# pi_mcu_powerBoard.net
KiCad netlist of a schematic drawn in EAGLE
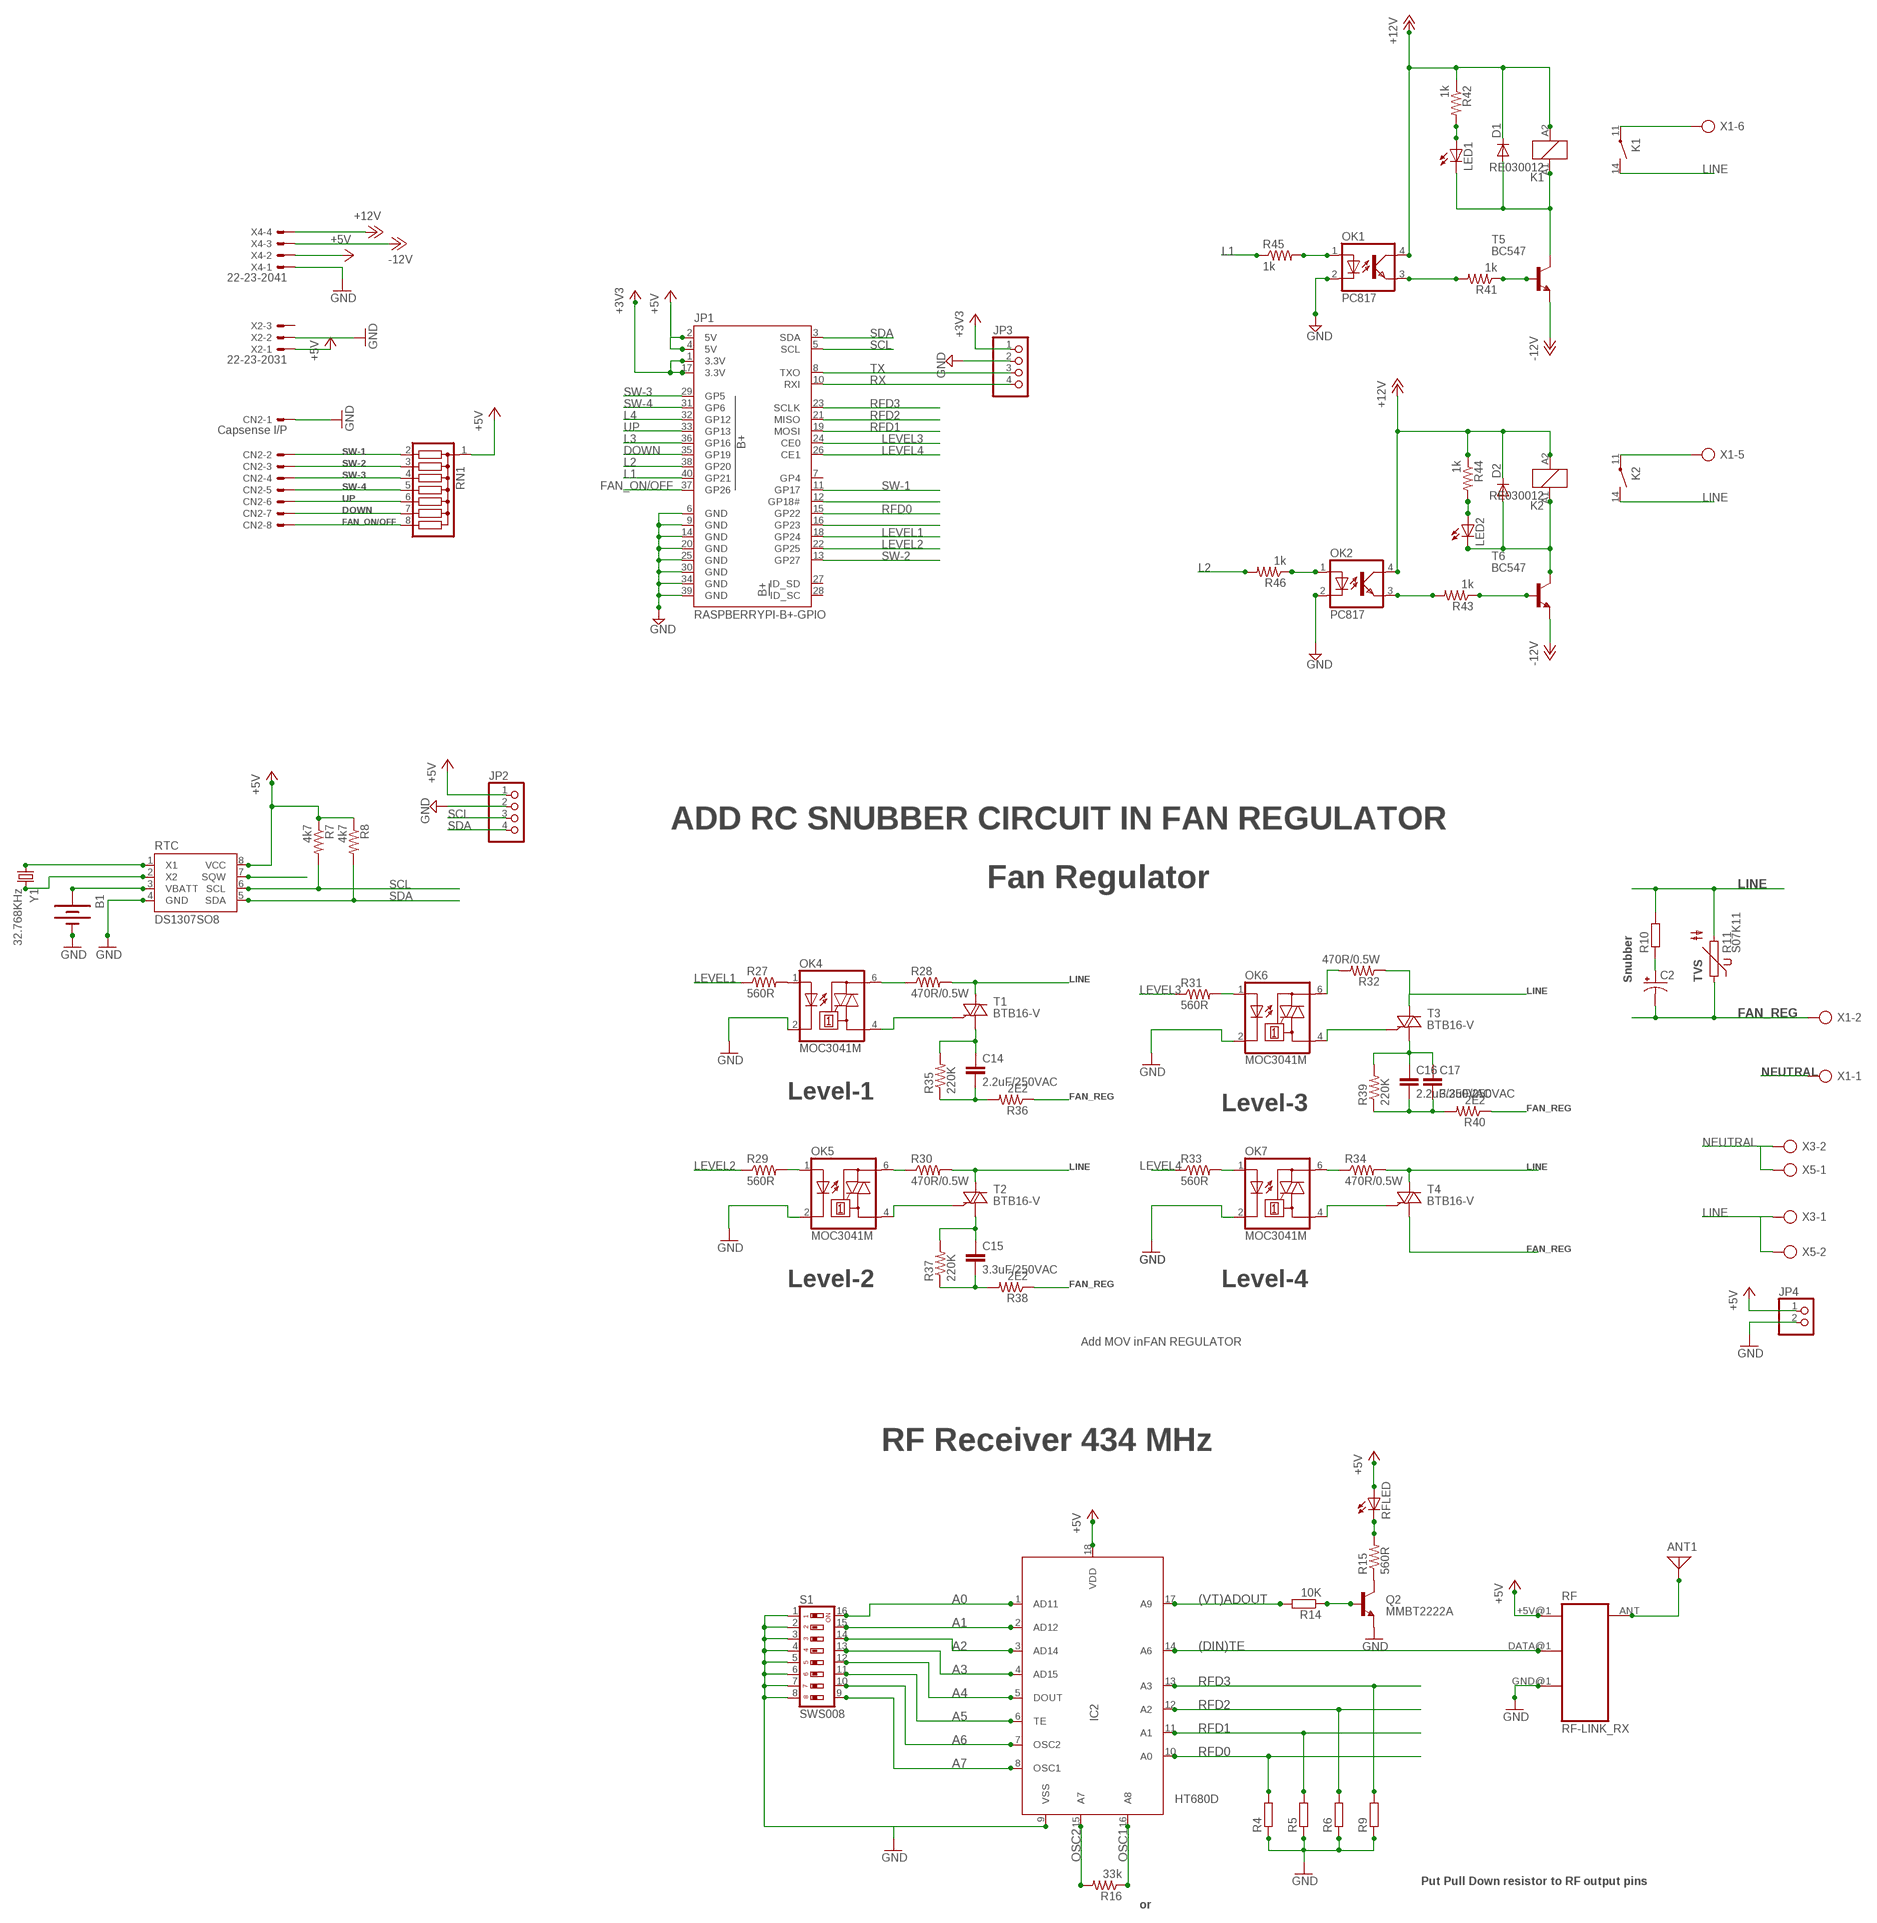
[diagram p0: schematic, sheet 1, part 1 of 2]
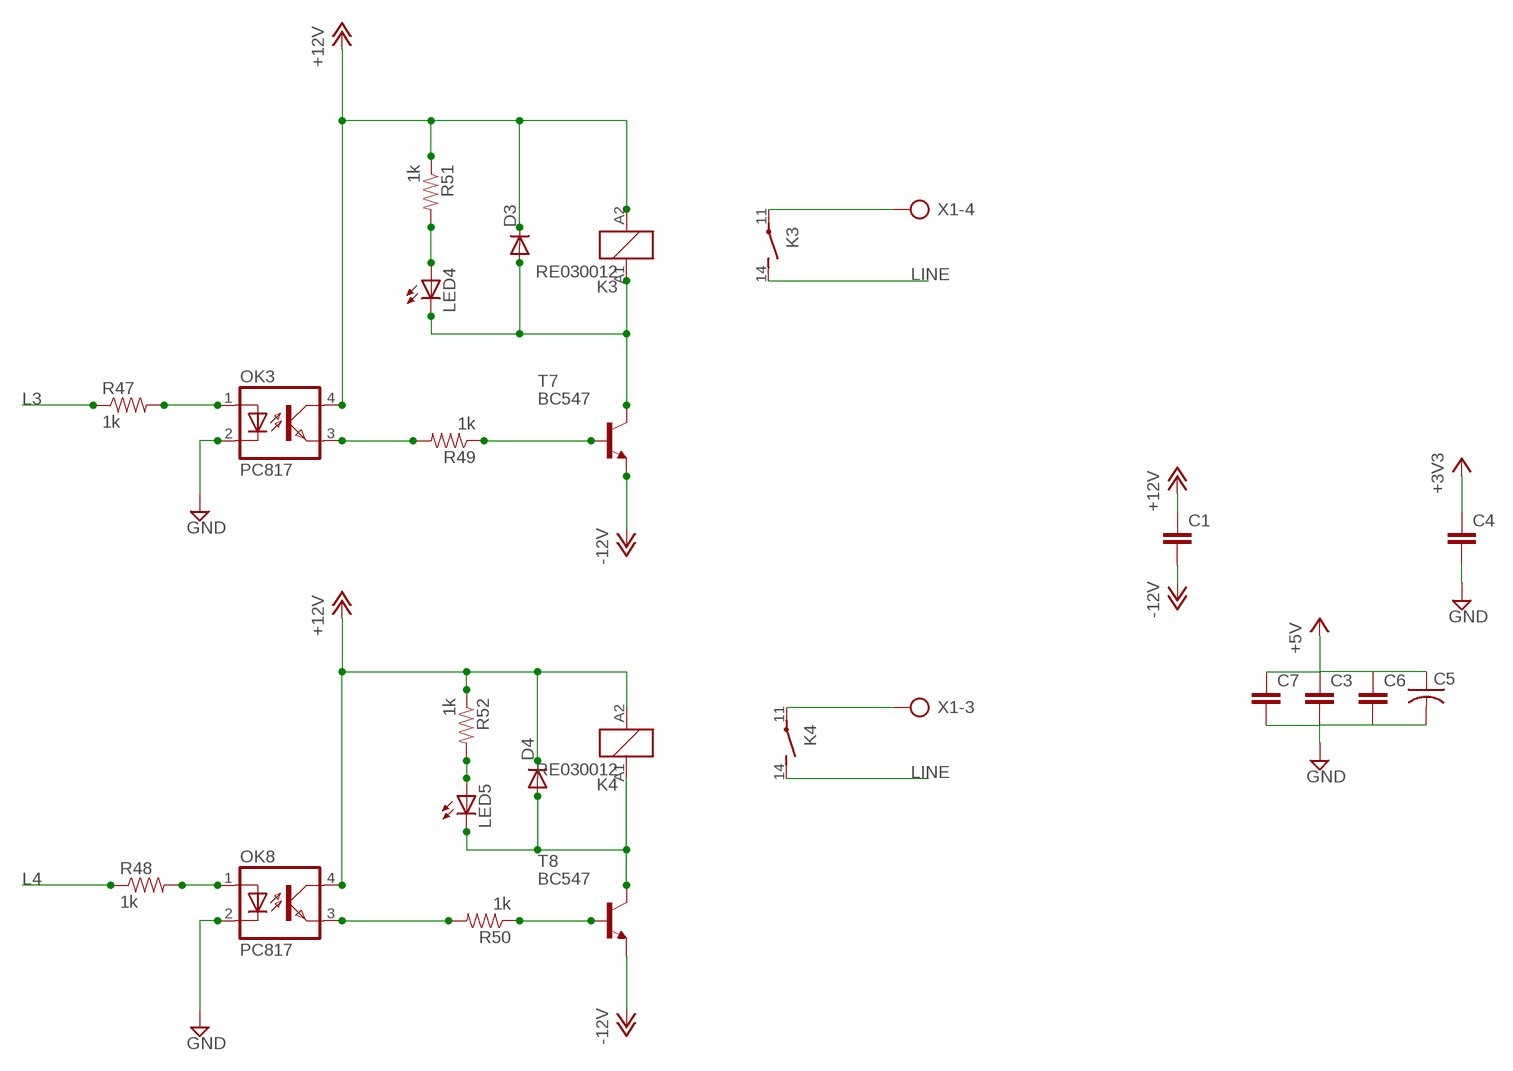
[diagram p1: schematic, sheet 1, part 2 of 2]

(export (version "E")
  (design (tool "Eeschema 10.0.6"))
  (components
    (comp (ref "ANT1")
      (value "ANTENNA")
      (footprint "eagle-import:PAD-01")
      (libsource (lib "eagle-import") (part "ANTENNA"))
    )
    (comp (ref "B1")
      (value "BATTERY20SMD")
      (footprint "eagle-import:BATTCON_20MM")
      (libsource (lib "eagle-import") (part "BATTERY20SMD"))
    )
    (comp (ref "C1")
      (value "C-EUC1206")
      (footprint "eagle-import:C1206")
      (libsource (lib "eagle-import") (part "C-EUC1206"))
    )
    (comp (ref "C2")
      (value "CPOL-USE5-9VAXIAL")
      (footprint "eagle-import:E5R")
      (libsource (lib "eagle-import") (part "CPOL-USE5-9VAXIAL"))
    )
    (comp (ref "C3")
      (value "C-EUC1206")
      (footprint "eagle-import:C1206")
      (libsource (lib "eagle-import") (part "C-EUC1206"))
    )
    (comp (ref "C4")
      (value "C-EUC1206")
      (footprint "eagle-import:C1206")
      (libsource (lib "eagle-import") (part "C-EUC1206"))
    )
    (comp (ref "C5")
      (value "C-USC1206")
      (footprint "eagle-import:C1206")
      (libsource (lib "eagle-import") (part "C-USC1206"))
    )
    (comp (ref "C6")
      (value "C-EUC1206")
      (footprint "eagle-import:C1206")
      (libsource (lib "eagle-import") (part "C-EUC1206"))
    )
    (comp (ref "C7")
      (value "C-EUC1206")
      (footprint "eagle-import:C1206")
      (libsource (lib "eagle-import") (part "C-EUC1206"))
    )
    (comp (ref "C14")
      (value "2.2uF/250VAC")
      (footprint "eagle-import:C27.5B9")
      (libsource (lib "eagle-import") (part "C27/9"))
    )
    (comp (ref "C15")
      (value "3.3uF/250VAC")
      (footprint "eagle-import:C27.5B9")
      (libsource (lib "eagle-import") (part "C27/9"))
    )
    (comp (ref "C16")
      (value "2.2uF/250VAC")
      (footprint "eagle-import:C27.5B9")
      (libsource (lib "eagle-import") (part "C27/9"))
    )
    (comp (ref "C17")
      (value "3.3uF/250VAC")
      (footprint "eagle-import:C27.5B9")
      (libsource (lib "eagle-import") (part "C27/9"))
    )
    (comp (ref "CN2")
      (value "Capsense I/P")
      (footprint "eagle-import:22-23-2081")
      (fields (field (name "MF") "MOLEX") (field (name "MPN") "22-23-2081"))
      (libsource (lib "eagle-import") (part "22-23-2081"))
    )
    (comp (ref "D1")
      (value "DIODE-D-2.5")
      (footprint "eagle-import:D-2.5")
      (libsource (lib "eagle-import") (part "DIODE-D-2.5"))
    )
    (comp (ref "D2")
      (value "DIODE-D-2.5")
      (footprint "eagle-import:D-2.5")
      (libsource (lib "eagle-import") (part "DIODE-D-2.5"))
    )
    (comp (ref "D3")
      (value "DIODE-D-2.5")
      (footprint "eagle-import:D-2.5")
      (libsource (lib "eagle-import") (part "DIODE-D-2.5"))
    )
    (comp (ref "D4")
      (value "DIODE-D-2.5")
      (footprint "eagle-import:D-2.5")
      (libsource (lib "eagle-import") (part "DIODE-D-2.5"))
    )
    (comp (ref "IC2")
      (value "HT680D")
      (footprint "eagle-import:SOP18")
      (libsource (lib "eagle-import") (part "HT680D"))
    )
    (comp (ref "JP1")
      (value "RASPBERRYPI-B+-GPIO")
      (footprint "eagle-import:2X20-SHROUDED")
      (libsource (lib "eagle-import") (part "RASPBERRYPI-B+-GPIO"))
    )
    (comp (ref "JP2")
      (value "PINHD-1X4")
      (footprint "eagle-import:1X04")
      (libsource (lib "eagle-import") (part "PINHD-1X4"))
    )
    (comp (ref "JP3")
      (value "PINHD-1X4")
      (footprint "eagle-import:1X04")
      (libsource (lib "eagle-import") (part "PINHD-1X4"))
    )
    (comp (ref "JP4")
      (value "PINHD-1X2")
      (footprint "eagle-import:1X02")
      (libsource (lib "eagle-import") (part "PINHD-1X2"))
    )
    (comp (ref "K1")
      (value "RE030012")
      (footprint "eagle-import:RE-SCHRACK")
      (fields (field (name "MF") "TYCO ELECTRONICS"))
      (libsource (lib "eagle-import") (part "RE030012"))
    )
    (comp (ref "K2")
      (value "RE030012")
      (footprint "eagle-import:RE-SCHRACK")
      (fields (field (name "MF") "TYCO ELECTRONICS"))
      (libsource (lib "eagle-import") (part "RE030012"))
    )
    (comp (ref "K3")
      (value "RE030012")
      (footprint "eagle-import:RE-SCHRACK")
      (fields (field (name "MF") "TYCO ELECTRONICS"))
      (libsource (lib "eagle-import") (part "RE030012"))
    )
    (comp (ref "K4")
      (value "RE030012")
      (footprint "eagle-import:RE-SCHRACK")
      (fields (field (name "MF") "TYCO ELECTRONICS"))
      (libsource (lib "eagle-import") (part "RE030012"))
    )
    (comp (ref "LED1")
      (value "LED3MM")
      (footprint "eagle-import:LED3MM")
      (libsource (lib "eagle-import") (part "LED3MM"))
    )
    (comp (ref "LED2")
      (value "LED3MM")
      (footprint "eagle-import:LED3MM")
      (libsource (lib "eagle-import") (part "LED3MM"))
    )
    (comp (ref "LED4")
      (value "LED3MM")
      (footprint "eagle-import:LED3MM")
      (libsource (lib "eagle-import") (part "LED3MM"))
    )
    (comp (ref "LED5")
      (value "LED3MM")
      (footprint "eagle-import:LED3MM")
      (libsource (lib "eagle-import") (part "LED3MM"))
    )
    (comp (ref "OK1")
      (value "PC817")
      (footprint "eagle-import:DIL04")
      (fields (field (name "MPN") "PC817X4J000F"))
      (libsource (lib "eagle-import") (part "PC817"))
    )
    (comp (ref "OK2")
      (value "PC817")
      (footprint "eagle-import:DIL04")
      (fields (field (name "MPN") "PC817X4J000F"))
      (libsource (lib "eagle-import") (part "PC817"))
    )
    (comp (ref "OK3")
      (value "PC817")
      (footprint "eagle-import:DIL04")
      (fields (field (name "MPN") "PC817X4J000F"))
      (libsource (lib "eagle-import") (part "PC817"))
    )
    (comp (ref "OK4")
      (value "MOC3041M")
      (footprint "eagle-import:DIL06")
      (fields
        (field (name "MF") "FAIRCHILD SEMICONDUCTOR")
        (field (name "MPN") "MOC3041M")
        (field (name "OC_FARNELL") "1086677")
        (field (name "OC_NEWARK") "78K6090")
      )
      (libsource (lib "eagle-import") (part "MOC3041M"))
    )
    (comp (ref "OK5")
      (value "MOC3041M")
      (footprint "eagle-import:DIL06")
      (fields
        (field (name "MF") "FAIRCHILD SEMICONDUCTOR")
        (field (name "MF_1") "FAIRCHILD SEMICONDUCTOR")
        (field (name "MPN") "MOC3031SM")
        (field (name "OC_FARNELL") "unknown")
        (field (name "OC_NEWARK") "34C1335")
      )
      (libsource (lib "eagle-import") (part "MOC3041M"))
    )
    (comp (ref "OK6")
      (value "MOC3041M")
      (footprint "eagle-import:DIL06")
      (fields
        (field (name "MF") "FAIRCHILD SEMICONDUCTOR")
        (field (name "MF_1") "FAIRCHILD SEMICONDUCTOR")
        (field (name "MPN") "MOC3031SM")
        (field (name "OC_FARNELL") "unknown")
        (field (name "OC_NEWARK") "34C1335")
      )
      (libsource (lib "eagle-import") (part "MOC3041M"))
    )
    (comp (ref "OK7")
      (value "MOC3041M")
      (footprint "eagle-import:DIL06")
      (fields
        (field (name "MF") "FAIRCHILD SEMICONDUCTOR")
        (field (name "MF_1") "FAIRCHILD SEMICONDUCTOR")
        (field (name "MPN") "MOC3031SM")
        (field (name "OC_FARNELL") "unknown")
        (field (name "OC_NEWARK") "34C1335")
      )
      (libsource (lib "eagle-import") (part "MOC3041M"))
    )
    (comp (ref "OK8")
      (value "PC817")
      (footprint "eagle-import:DIL04")
      (fields (field (name "MPN") "PC817X4J000F"))
      (libsource (lib "eagle-import") (part "PC817"))
    )
    (comp (ref "Q2")
      (value "MMBT2222A")
      (footprint "eagle-import:SOT23-3")
      (libsource (lib "eagle-import") (part "TRANSISTOR_NPNMMBT2222A"))
    )
    (comp (ref "R4")
      (value "R-EU_0207/10")
      (footprint "eagle-import:0207_10")
      (libsource (lib "eagle-import") (part "R-EU_0207/10"))
    )
    (comp (ref "R5")
      (value "R-EU_0207/10")
      (footprint "eagle-import:0207_10")
      (libsource (lib "eagle-import") (part "R-EU_0207/10"))
    )
    (comp (ref "R6")
      (value "R-EU_0207/10")
      (footprint "eagle-import:0207_10")
      (libsource (lib "eagle-import") (part "R-EU_0207/10"))
    )
    (comp (ref "R7")
      (value "4k7")
      (footprint "eagle-import:1206")
      (libsource (lib "eagle-import") (part "RESISTOR1206"))
    )
    (comp (ref "R8")
      (value "4k7")
      (footprint "eagle-import:1206")
      (libsource (lib "eagle-import") (part "RESISTOR1206"))
    )
    (comp (ref "R9")
      (value "R-EU_0207/10")
      (footprint "eagle-import:0207_10")
      (libsource (lib "eagle-import") (part "R-EU_0207/10"))
    )
    (comp (ref "R10")
      (value "R-EU_0411/3V")
      (footprint "eagle-import:0411V")
      (libsource (lib "eagle-import") (part "R-EU_0411/3V"))
    )
    (comp (ref "R11")
      (value "S07K11")
      (footprint "eagle-import:S07K11")
      (libsource (lib "eagle-import") (part "S07K11"))
    )
    (comp (ref "R14")
      (value "10K")
      (footprint "eagle-import:0207_10")
      (libsource (lib "eagle-import") (part "R-EU_0207/10"))
    )
    (comp (ref "R15")
      (value "560R")
      (footprint "eagle-import:1206")
      (libsource (lib "eagle-import") (part "SparkFun-Resistors_RESISTOR1206"))
    )
    (comp (ref "R16")
      (value "33k")
      (footprint "eagle-import:1206")
      (libsource (lib "eagle-import") (part "SparkFun-Resistors_RESISTOR1206"))
    )
    (comp (ref "R27")
      (value "560R")
      (footprint "eagle-import:1206")
      (libsource (lib "eagle-import") (part "SparkFun-Resistors_RESISTOR1206"))
    )
    (comp (ref "R28")
      (value "470R/0.5W")
      (footprint "eagle-import:0411V")
      (libsource (lib "eagle-import") (part "R-US_0411/3V"))
    )
    (comp (ref "R29")
      (value "560R")
      (footprint "eagle-import:1206")
      (libsource (lib "eagle-import") (part "SparkFun-Resistors_RESISTOR1206"))
    )
    (comp (ref "R30")
      (value "470R/0.5W")
      (footprint "eagle-import:0411V")
      (libsource (lib "eagle-import") (part "R-US_0411/3V"))
    )
    (comp (ref "R31")
      (value "560R")
      (footprint "eagle-import:1206")
      (libsource (lib "eagle-import") (part "SparkFun-Resistors_RESISTOR1206"))
    )
    (comp (ref "R32")
      (value "470R/0.5W")
      (footprint "eagle-import:0411V")
      (libsource (lib "eagle-import") (part "R-US_0411/3V"))
    )
    (comp (ref "R33")
      (value "560R")
      (footprint "eagle-import:1206")
      (libsource (lib "eagle-import") (part "SparkFun-Resistors_RESISTOR1206"))
    )
    (comp (ref "R34")
      (value "470R/0.5W")
      (footprint "eagle-import:0411V")
      (libsource (lib "eagle-import") (part "R-US_0411/3V"))
    )
    (comp (ref "R35")
      (value "220K")
      (footprint "eagle-import:1206")
      (libsource (lib "eagle-import") (part "SparkFun-Resistors_RESISTOR1206"))
    )
    (comp (ref "R36")
      (value "2E2")
      (footprint "eagle-import:1206")
      (libsource (lib "eagle-import") (part "SparkFun-Resistors_RESISTOR1206"))
    )
    (comp (ref "R37")
      (value "220K")
      (footprint "eagle-import:1206")
      (libsource (lib "eagle-import") (part "SparkFun-Resistors_RESISTOR1206"))
    )
    (comp (ref "R38")
      (value "2E2")
      (footprint "eagle-import:1206")
      (libsource (lib "eagle-import") (part "SparkFun-Resistors_RESISTOR1206"))
    )
    (comp (ref "R39")
      (value "220K")
      (footprint "eagle-import:1206")
      (libsource (lib "eagle-import") (part "SparkFun-Resistors_RESISTOR1206"))
    )
    (comp (ref "R40")
      (value "2E2")
      (footprint "eagle-import:1206")
      (libsource (lib "eagle-import") (part "SparkFun-Resistors_RESISTOR1206"))
    )
    (comp (ref "R41")
      (value "1k")
      (footprint "eagle-import:1206")
      (libsource (lib "eagle-import") (part "SparkFun-Resistors_RESISTOR1206"))
    )
    (comp (ref "R42")
      (value "1k")
      (footprint "eagle-import:1206")
      (libsource (lib "eagle-import") (part "SparkFun-Resistors_RESISTOR1206"))
    )
    (comp (ref "R43")
      (value "1k")
      (footprint "eagle-import:1206")
      (libsource (lib "eagle-import") (part "SparkFun-Resistors_RESISTOR1206"))
    )
    (comp (ref "R44")
      (value "1k")
      (footprint "eagle-import:1206")
      (libsource (lib "eagle-import") (part "SparkFun-Resistors_RESISTOR1206"))
    )
    (comp (ref "R45")
      (value "1k")
      (footprint "eagle-import:1206")
      (libsource (lib "eagle-import") (part "SparkFun-Resistors_RESISTOR1206"))
    )
    (comp (ref "R46")
      (value "1k")
      (footprint "eagle-import:1206")
      (libsource (lib "eagle-import") (part "SparkFun-Resistors_RESISTOR1206"))
    )
    (comp (ref "R47")
      (value "1k")
      (footprint "eagle-import:1206")
      (libsource (lib "eagle-import") (part "SparkFun-Resistors_RESISTOR1206"))
    )
    (comp (ref "R48")
      (value "1k")
      (footprint "eagle-import:1206")
      (libsource (lib "eagle-import") (part "SparkFun-Resistors_RESISTOR1206"))
    )
    (comp (ref "R49")
      (value "1k")
      (footprint "eagle-import:1206")
      (libsource (lib "eagle-import") (part "SparkFun-Resistors_RESISTOR1206"))
    )
    (comp (ref "R50")
      (value "1k")
      (footprint "eagle-import:1206")
      (libsource (lib "eagle-import") (part "SparkFun-Resistors_RESISTOR1206"))
    )
    (comp (ref "R51")
      (value "1k")
      (footprint "eagle-import:1206")
      (libsource (lib "eagle-import") (part "SparkFun-Resistors_RESISTOR1206"))
    )
    (comp (ref "R52")
      (value "1k")
      (footprint "eagle-import:1206")
      (libsource (lib "eagle-import") (part "SparkFun-Resistors_RESISTOR1206"))
    )
    (comp (ref "RF")
      (value "RF-LINK_RX")
      (footprint "eagle-import:RF-LINK_RX")
      (libsource (lib "eagle-import") (part "RF-LINK_RX"))
    )
    (comp (ref "RFLED")
      (value "LED3MM")
      (footprint "eagle-import:LED3MM")
      (libsource (lib "eagle-import") (part "led_LED3MM"))
    )
    (comp (ref "RN1")
      (value "G07R")
      (footprint "eagle-import:SIL8")
      (libsource (lib "eagle-import") (part "G07R"))
    )
    (comp (ref "RTC")
      (value "DS1307SO8")
      (footprint "eagle-import:SO08")
      (libsource (lib "eagle-import") (part "DS1307SO8"))
    )
    (comp (ref "S1")
      (value "SWS008")
      (footprint "eagle-import:SMS-008")
      (libsource (lib "eagle-import") (part "SWS008"))
    )
    (comp (ref "T1")
      (value "BTB16-V")
      (footprint "eagle-import:TO220BV")
      (libsource (lib "eagle-import") (part "BT138-V"))
    )
    (comp (ref "T2")
      (value "BTB16-V")
      (footprint "eagle-import:TO220BV")
      (libsource (lib "eagle-import") (part "BT138-V"))
    )
    (comp (ref "T3")
      (value "BTB16-V")
      (footprint "eagle-import:TO220BV")
      (libsource (lib "eagle-import") (part "BT138-V"))
    )
    (comp (ref "T4")
      (value "BTB16-V")
      (footprint "eagle-import:TO220BV")
      (libsource (lib "eagle-import") (part "BT138-V"))
    )
    (comp (ref "T5")
      (value "BC547")
      (footprint "eagle-import:TO92")
      (libsource (lib "eagle-import") (part "BC547"))
    )
    (comp (ref "T6")
      (value "BC547")
      (footprint "eagle-import:TO92")
      (libsource (lib "eagle-import") (part "BC547"))
    )
    (comp (ref "T7")
      (value "BC547")
      (footprint "eagle-import:TO92")
      (libsource (lib "eagle-import") (part "BC547"))
    )
    (comp (ref "T8")
      (value "BC547")
      (footprint "eagle-import:TO92")
      (libsource (lib "eagle-import") (part "BC547"))
    )
    (comp (ref "X1")
      (value "AK300/6")
      (footprint "eagle-import:AK300_6")
      (libsource (lib "eagle-import") (part "AK300/6"))
    )
    (comp (ref "X2")
      (value "22-23-2031")
      (footprint "eagle-import:22-23-2031")
      (fields (field (name "MF") "MOLEX"))
      (libsource (lib "eagle-import") (part "22-23-2031"))
    )
    (comp (ref "X3")
      (value "AK300/2")
      (footprint "eagle-import:AK300_2")
      (fields (field (name "OC_FARNELL") "unknown") (field (name "OC_NEWARK") "unknown"))
      (libsource (lib "eagle-import") (part "AK300/2"))
    )
    (comp (ref "X4")
      (value "22-23-2041")
      (footprint "eagle-import:22-23-2041")
      (fields (field (name "MF") "MOLEX"))
      (libsource (lib "eagle-import") (part "22-23-2041"))
    )
    (comp (ref "X5")
      (value "AK300/2")
      (footprint "eagle-import:AK300_2")
      (libsource (lib "eagle-import") (part "AK300/2"))
    )
    (comp (ref "Y1")
      (value "32.768KHz")
      (footprint "eagle-import:TC26H")
      (libsource (lib "eagle-import") (part "CRYSTALTC26H"))
    )
  )
  (nets
    (net (code "1") (name "+3V3") (class "Default")
      (node (ref "C4") (pin "1") (pinfunction "1_1") (pintype "passive"))
      (node (ref "JP1") (pin "1") (pinfunction "3.3V_1") (pintype "power_in"))
      (node (ref "JP1") (pin "17") (pinfunction "3.3V_17") (pintype "power_in"))
      (node (ref "JP3") (pin "1") (pinfunction "1_1") (pintype "passive"))
    )
    (net (code "2") (name "+5V") (class "Default")
      (node (ref "C3") (pin "1") (pinfunction "1_1") (pintype "passive"))
      (node (ref "C5") (pin "1") (pinfunction "1_1") (pintype "passive"))
      (node (ref "C6") (pin "1") (pinfunction "1_1") (pintype "passive"))
      (node (ref "C7") (pin "1") (pinfunction "1_1") (pintype "passive"))
      (node (ref "IC2") (pin "18") (pinfunction "VDD_18") (pintype "power_in"))
      (node (ref "JP1") (pin "2") (pinfunction "5V_2") (pintype "power_in"))
      (node (ref "JP1") (pin "4") (pinfunction "5V_4") (pintype "power_in"))
      (node (ref "JP2") (pin "1") (pinfunction "1_1") (pintype "passive"))
      (node (ref "JP4") (pin "1") (pinfunction "1_1") (pintype "passive"))
      (node (ref "R7") (pin "1") (pinfunction "1_1") (pintype "passive"))
      (node (ref "R8") (pin "1") (pinfunction "1_1") (pintype "passive"))
      (node (ref "RF") (pin "+5V@1") (pinfunction "+5V_+5V@1") (pintype "power_in"))
      (node (ref "RFLED") (pin "A") (pinfunction "A_A") (pintype "passive"))
      (node (ref "RN1") (pin "1") (pinfunction "1_1") (pintype "passive"))
      (node (ref "RTC") (pin "8") (pinfunction "VCC_8") (pintype "bidirectional"))
      (node (ref "X2") (pin "1") (pinfunction "S_1") (pintype "passive"))
      (node (ref "X4") (pin "2") (pinfunction "S_2") (pintype "passive"))
    )
    (net (code "3") (name "+12V") (class "Default")
      (node (ref "C1") (pin "1") (pinfunction "1_1") (pintype "passive"))
      (node (ref "D1") (pin "C") (pinfunction "C_C") (pintype "passive"))
      (node (ref "D2") (pin "C") (pinfunction "C_C") (pintype "passive"))
      (node (ref "D3") (pin "C") (pinfunction "C_C") (pintype "passive"))
      (node (ref "D4") (pin "C") (pinfunction "C_C") (pintype "passive"))
      (node (ref "K1") (pin "A2") (pinfunction "2_A2") (pintype "passive"))
      (node (ref "K2") (pin "A2") (pinfunction "2_A2") (pintype "passive"))
      (node (ref "K3") (pin "A2") (pinfunction "2_A2") (pintype "passive"))
      (node (ref "K4") (pin "A2") (pinfunction "2_A2") (pintype "passive"))
      (node (ref "OK1") (pin "4") (pinfunction "COL_4") (pintype "passive"))
      (node (ref "OK2") (pin "4") (pinfunction "COL_4") (pintype "passive"))
      (node (ref "OK3") (pin "4") (pinfunction "COL_4") (pintype "passive"))
      (node (ref "OK8") (pin "4") (pinfunction "COL_4") (pintype "passive"))
      (node (ref "R42") (pin "1") (pinfunction "1_1") (pintype "passive"))
      (node (ref "R44") (pin "1") (pinfunction "1_1") (pintype "passive"))
      (node (ref "R51") (pin "1") (pinfunction "1_1") (pintype "passive"))
      (node (ref "R52") (pin "1") (pinfunction "1_1") (pintype "passive"))
      (node (ref "X4") (pin "4") (pinfunction "S_4") (pintype "passive"))
    )
    (net (code "4") (name "-12V") (class "Default")
      (node (ref "C1") (pin "2") (pinfunction "2_2") (pintype "passive"))
      (node (ref "T5") (pin "1") (pinfunction "E_1") (pintype "passive"))
      (node (ref "T6") (pin "1") (pinfunction "E_1") (pintype "passive"))
      (node (ref "T7") (pin "1") (pinfunction "E_1") (pintype "passive"))
      (node (ref "T8") (pin "1") (pinfunction "E_1") (pintype "passive"))
      (node (ref "X4") (pin "3") (pinfunction "S_3") (pintype "passive"))
    )
    (net (code "5") (name "/(DIN)TE") (class "Default")
      (node (ref "IC2") (pin "14") (pinfunction "A6_14") (pintype "input"))
      (node (ref "RF") (pin "DATA@1") (pinfunction "DATA_DATA@1") (pintype "input"))
    )
    (net (code "6") (name "/(VT)ADOUT") (class "Default")
      (node (ref "IC2") (pin "17") (pinfunction "A9_17") (pintype "input"))
      (node (ref "R14") (pin "2") (pinfunction "2_2") (pintype "passive"))
    )
    (net (code "7") (name "/A0") (class "Default")
      (node (ref "IC2") (pin "1") (pinfunction "AD11_1") (pintype "input"))
      (node (ref "S1") (pin "16") (pinfunction "16_16") (pintype "passive"))
    )
    (net (code "8") (name "/A1") (class "Default")
      (node (ref "IC2") (pin "2") (pinfunction "AD12_2") (pintype "input"))
      (node (ref "S1") (pin "15") (pinfunction "15_15") (pintype "passive"))
    )
    (net (code "9") (name "/A2") (class "Default")
      (node (ref "IC2") (pin "3") (pinfunction "AD14_3") (pintype "input"))
      (node (ref "S1") (pin "14") (pinfunction "14_14") (pintype "passive"))
    )
    (net (code "10") (name "/A3") (class "Default")
      (node (ref "IC2") (pin "4") (pinfunction "AD15_4") (pintype "input"))
      (node (ref "S1") (pin "13") (pinfunction "13_13") (pintype "passive"))
    )
    (net (code "11") (name "/A4") (class "Default")
      (node (ref "IC2") (pin "5") (pinfunction "DOUT_5") (pintype "input"))
      (node (ref "S1") (pin "12") (pinfunction "12_12") (pintype "passive"))
    )
    (net (code "12") (name "/A5") (class "Default")
      (node (ref "IC2") (pin "6") (pinfunction "TE_6") (pintype "input"))
      (node (ref "S1") (pin "11") (pinfunction "11_11") (pintype "passive"))
    )
    (net (code "13") (name "/A6") (class "Default")
      (node (ref "IC2") (pin "7") (pinfunction "OSC2_7") (pintype "output"))
      (node (ref "S1") (pin "10") (pinfunction "10_10") (pintype "passive"))
    )
    (net (code "14") (name "/A7") (class "Default")
      (node (ref "IC2") (pin "8") (pinfunction "OSC1_8") (pintype "input"))
      (node (ref "S1") (pin "9") (pinfunction "9_9") (pintype "passive"))
    )
    (net (code "15") (name "/DOWN") (class "Default")
      (node (ref "CN2") (pin "7") (pinfunction "S_7") (pintype "passive"))
      (node (ref "JP1") (pin "35") (pinfunction "GP19_35") (pintype "bidirectional"))
      (node (ref "RN1") (pin "7") (pinfunction "7_7") (pintype "passive"))
    )
    (net (code "16") (name "/FAN_ON{slash}OFF") (class "Default")
      (node (ref "CN2") (pin "8") (pinfunction "S_8") (pintype "passive"))
      (node (ref "JP1") (pin "37") (pinfunction "GP26_37") (pintype "bidirectional"))
      (node (ref "RN1") (pin "8") (pinfunction "8_8") (pintype "passive"))
    )
    (net (code "17") (name "/FAN_REG") (class "Default")
      (node (ref "C2") (pin "-") (pinfunction "-_-") (pintype "passive"))
      (node (ref "R11") (pin "1") (pinfunction "1_1") (pintype "passive"))
      (node (ref "R36") (pin "1") (pinfunction "1_1") (pintype "passive"))
      (node (ref "R38") (pin "1") (pinfunction "1_1") (pintype "passive"))
      (node (ref "R40") (pin "1") (pinfunction "1_1") (pintype "passive"))
      (node (ref "T4") (pin "T1") (pinfunction "A1_T1") (pintype "passive"))
      (node (ref "X1") (pin "2") (pinfunction "KL_2") (pintype "passive"))
    )
    (net (code "18") (name "/L1") (class "Default")
      (node (ref "JP1") (pin "40") (pinfunction "GP21_40") (pintype "bidirectional"))
      (node (ref "R45") (pin "1") (pinfunction "1_1") (pintype "passive"))
    )
    (net (code "19") (name "/L2") (class "Default")
      (node (ref "JP1") (pin "38") (pinfunction "GP20_38") (pintype "bidirectional"))
      (node (ref "R46") (pin "2") (pinfunction "2_2") (pintype "passive"))
    )
    (net (code "20") (name "/L3") (class "Default")
      (node (ref "JP1") (pin "36") (pinfunction "GP16_36") (pintype "bidirectional"))
      (node (ref "R47") (pin "1") (pinfunction "1_1") (pintype "passive"))
    )
    (net (code "21") (name "/L4") (class "Default")
      (node (ref "JP1") (pin "32") (pinfunction "GP12_32") (pintype "bidirectional"))
      (node (ref "R48") (pin "1") (pinfunction "1_1") (pintype "passive"))
    )
    (net (code "22") (name "/LEVEL1") (class "Default")
      (node (ref "JP1") (pin "18") (pinfunction "GP24_18") (pintype "bidirectional"))
      (node (ref "R27") (pin "1") (pinfunction "1_1") (pintype "passive"))
    )
    (net (code "23") (name "/LEVEL2") (class "Default")
      (node (ref "JP1") (pin "22") (pinfunction "GP25_22") (pintype "bidirectional"))
      (node (ref "R29") (pin "1") (pinfunction "1_1") (pintype "passive"))
    )
    (net (code "24") (name "/LEVEL3") (class "Default")
      (node (ref "JP1") (pin "24") (pinfunction "CE0_24") (pintype "output"))
      (node (ref "R31") (pin "1") (pinfunction "1_1") (pintype "passive"))
    )
    (net (code "25") (name "/LEVEL4") (class "Default")
      (node (ref "JP1") (pin "26") (pinfunction "CE1_26") (pintype "output"))
      (node (ref "R33") (pin "1") (pinfunction "1_1") (pintype "passive"))
    )
    (net (code "26") (name "/LINE") (class "Default")
      (node (ref "K1") (pin "14") (pinfunction "S_14") (pintype "passive"))
      (node (ref "K2") (pin "14") (pinfunction "S_14") (pintype "passive"))
      (node (ref "K3") (pin "14") (pinfunction "S_14") (pintype "passive"))
      (node (ref "K4") (pin "14") (pinfunction "S_14") (pintype "passive"))
      (node (ref "R10") (pin "2") (pinfunction "2_2") (pintype "passive"))
      (node (ref "R11") (pin "2") (pinfunction "2_2") (pintype "passive"))
      (node (ref "R28") (pin "2") (pinfunction "2_2") (pintype "passive"))
      (node (ref "R30") (pin "2") (pinfunction "2_2") (pintype "passive"))
      (node (ref "R32") (pin "1") (pinfunction "1_1") (pintype "passive"))
      (node (ref "R34") (pin "2") (pinfunction "2_2") (pintype "passive"))
      (node (ref "T1") (pin "T2") (pinfunction "A2_T2") (pintype "passive"))
      (node (ref "T2") (pin "T2") (pinfunction "A2_T2") (pintype "passive"))
      (node (ref "T3") (pin "T2") (pinfunction "A2_T2") (pintype "passive"))
      (node (ref "T4") (pin "T2") (pinfunction "A2_T2") (pintype "passive"))
      (node (ref "X3") (pin "1") (pinfunction "KL_1") (pintype "passive"))
      (node (ref "X5") (pin "2") (pinfunction "KL_2") (pintype "passive"))
    )
    (net (code "27") (name "/NEUTRAL") (class "Default")
      (node (ref "X1") (pin "1") (pinfunction "KL_1") (pintype "passive"))
      (node (ref "X3") (pin "2") (pinfunction "KL_2") (pintype "passive"))
      (node (ref "X5") (pin "1") (pinfunction "KL_1") (pintype "passive"))
    )
    (net (code "28") (name "/OSC1") (class "Default")
      (node (ref "IC2") (pin "16") (pinfunction "A8_16") (pintype "input"))
      (node (ref "R16") (pin "1") (pinfunction "1_1") (pintype "passive"))
    )
    (net (code "29") (name "/OSC2") (class "Default")
      (node (ref "IC2") (pin "15") (pinfunction "A7_15") (pintype "input"))
      (node (ref "R16") (pin "2") (pinfunction "2_2") (pintype "passive"))
    )
    (net (code "30") (name "/RFD0") (class "Default")
      (node (ref "IC2") (pin "10") (pinfunction "A0_10") (pintype "input"))
      (node (ref "JP1") (pin "15") (pinfunction "GP22_15") (pintype "bidirectional"))
      (node (ref "R4") (pin "2") (pinfunction "2_2") (pintype "passive"))
    )
    (net (code "31") (name "/RFD1") (class "Default")
      (node (ref "IC2") (pin "11") (pinfunction "A1_11") (pintype "input"))
      (node (ref "JP1") (pin "19") (pinfunction "MOSI_19") (pintype "output"))
      (node (ref "R5") (pin "2") (pinfunction "2_2") (pintype "passive"))
    )
    (net (code "32") (name "/RFD2") (class "Default")
      (node (ref "IC2") (pin "12") (pinfunction "A2_12") (pintype "input"))
      (node (ref "JP1") (pin "21") (pinfunction "MISO_21") (pintype "input"))
      (node (ref "R6") (pin "2") (pinfunction "2_2") (pintype "passive"))
    )
    (net (code "33") (name "/RFD3") (class "Default")
      (node (ref "IC2") (pin "13") (pinfunction "A3_13") (pintype "input"))
      (node (ref "JP1") (pin "23") (pinfunction "SCLK_23") (pintype "output"))
      (node (ref "R9") (pin "2") (pinfunction "2_2") (pintype "passive"))
    )
    (net (code "34") (name "/RX") (class "Default")
      (node (ref "JP1") (pin "10") (pinfunction "RXI_10") (pintype "input"))
      (node (ref "JP3") (pin "4") (pinfunction "4_4") (pintype "passive"))
    )
    (net (code "35") (name "/SCL") (class "Default")
      (node (ref "JP1") (pin "5") (pinfunction "SCL_5") (pintype "bidirectional"))
      (node (ref "JP2") (pin "3") (pinfunction "3_3") (pintype "passive"))
      (node (ref "R7") (pin "2") (pinfunction "2_2") (pintype "passive"))
      (node (ref "RTC") (pin "6") (pinfunction "SCL_6") (pintype "bidirectional"))
    )
    (net (code "36") (name "/SDA") (class "Default")
      (node (ref "JP1") (pin "3") (pinfunction "SDA_3") (pintype "bidirectional"))
      (node (ref "JP2") (pin "4") (pinfunction "4_4") (pintype "passive"))
      (node (ref "R8") (pin "2") (pinfunction "2_2") (pintype "passive"))
      (node (ref "RTC") (pin "5") (pinfunction "SDA_5") (pintype "bidirectional"))
    )
    (net (code "37") (name "/SW-1") (class "Default")
      (node (ref "CN2") (pin "2") (pinfunction "S_2") (pintype "passive"))
      (node (ref "JP1") (pin "11") (pinfunction "GP17_11") (pintype "bidirectional"))
      (node (ref "RN1") (pin "2") (pinfunction "2_2") (pintype "passive"))
    )
    (net (code "38") (name "/SW-2") (class "Default")
      (node (ref "CN2") (pin "3") (pinfunction "S_3") (pintype "passive"))
      (node (ref "JP1") (pin "13") (pinfunction "GP27_13") (pintype "bidirectional"))
      (node (ref "RN1") (pin "3") (pinfunction "3_3") (pintype "passive"))
    )
    (net (code "39") (name "/SW-3") (class "Default")
      (node (ref "CN2") (pin "4") (pinfunction "S_4") (pintype "passive"))
      (node (ref "JP1") (pin "29") (pinfunction "GP5_29") (pintype "bidirectional"))
      (node (ref "RN1") (pin "4") (pinfunction "4_4") (pintype "passive"))
    )
    (net (code "40") (name "/SW-4") (class "Default")
      (node (ref "CN2") (pin "5") (pinfunction "S_5") (pintype "passive"))
      (node (ref "JP1") (pin "31") (pinfunction "GP6_31") (pintype "bidirectional"))
      (node (ref "RN1") (pin "5") (pinfunction "5_5") (pintype "passive"))
    )
    (net (code "41") (name "/TX") (class "Default")
      (node (ref "JP1") (pin "8") (pinfunction "TXO_8") (pintype "output"))
      (node (ref "JP3") (pin "3") (pinfunction "3_3") (pintype "passive"))
    )
    (net (code "42") (name "/UP") (class "Default")
      (node (ref "CN2") (pin "6") (pinfunction "S_6") (pintype "passive"))
      (node (ref "JP1") (pin "33") (pinfunction "GP13_33") (pintype "bidirectional"))
      (node (ref "RN1") (pin "6") (pinfunction "6_6") (pintype "passive"))
    )
    (net (code "43") (name "GND") (class "Default")
      (node (ref "B1") (pin "2") (pinfunction "-_2") (pintype "power_in"))
      (node (ref "C3") (pin "2") (pinfunction "2_2") (pintype "passive"))
      (node (ref "C4") (pin "2") (pinfunction "2_2") (pintype "passive"))
      (node (ref "C5") (pin "2") (pinfunction "2_2") (pintype "passive"))
      (node (ref "C6") (pin "2") (pinfunction "2_2") (pintype "passive"))
      (node (ref "C7") (pin "2") (pinfunction "2_2") (pintype "passive"))
      (node (ref "CN2") (pin "1") (pinfunction "S_1") (pintype "passive"))
      (node (ref "IC2") (pin "9") (pinfunction "VSS_9") (pintype "power_in"))
      (node (ref "JP1") (pin "14") (pinfunction "GND_14") (pintype "power_in"))
      (node (ref "JP1") (pin "20") (pinfunction "GND_20") (pintype "power_in"))
      (node (ref "JP1") (pin "25") (pinfunction "GND_25") (pintype "power_in"))
      (node (ref "JP1") (pin "30") (pinfunction "GND_30") (pintype "power_in"))
      (node (ref "JP1") (pin "34") (pinfunction "GND_34") (pintype "power_in"))
      (node (ref "JP1") (pin "39") (pinfunction "GND_39") (pintype "power_in"))
      (node (ref "JP1") (pin "6") (pinfunction "GND_6") (pintype "power_in"))
      (node (ref "JP1") (pin "9") (pinfunction "GND_9") (pintype "power_in"))
      (node (ref "JP2") (pin "2") (pinfunction "2_2") (pintype "passive"))
      (node (ref "JP3") (pin "2") (pinfunction "2_2") (pintype "passive"))
      (node (ref "JP4") (pin "2") (pinfunction "2_2") (pintype "passive"))
      (node (ref "OK1") (pin "2") (pinfunction "C_2") (pintype "passive"))
      (node (ref "OK2") (pin "2") (pinfunction "C_2") (pintype "passive"))
      (node (ref "OK3") (pin "2") (pinfunction "C_2") (pintype "passive"))
      (node (ref "OK4") (pin "2") (pinfunction "C_2") (pintype "passive"))
      (node (ref "OK5") (pin "2") (pinfunction "C_2") (pintype "passive"))
      (node (ref "OK6") (pin "2") (pinfunction "C_2") (pintype "passive"))
      (node (ref "OK7") (pin "2") (pinfunction "C_2") (pintype "passive"))
      (node (ref "OK8") (pin "2") (pinfunction "C_2") (pintype "passive"))
      (node (ref "Q2") (pin "2") (pinfunction "E_2") (pintype "passive"))
      (node (ref "R4") (pin "1") (pinfunction "1_1") (pintype "passive"))
      (node (ref "R5") (pin "1") (pinfunction "1_1") (pintype "passive"))
      (node (ref "R6") (pin "1") (pinfunction "1_1") (pintype "passive"))
      (node (ref "R9") (pin "1") (pinfunction "1_1") (pintype "passive"))
      (node (ref "RF") (pin "GND@1") (pinfunction "GND_GND@1") (pintype "power_in"))
      (node (ref "RTC") (pin "4") (pinfunction "GND_4") (pintype "bidirectional"))
      (node (ref "S1") (pin "1") (pinfunction "1_1") (pintype "passive"))
      (node (ref "S1") (pin "2") (pinfunction "2_2") (pintype "passive"))
      (node (ref "S1") (pin "3") (pinfunction "3_3") (pintype "passive"))
      (node (ref "S1") (pin "4") (pinfunction "4_4") (pintype "passive"))
      (node (ref "S1") (pin "5") (pinfunction "5_5") (pintype "passive"))
      (node (ref "S1") (pin "6") (pinfunction "6_6") (pintype "passive"))
      (node (ref "S1") (pin "7") (pinfunction "7_7") (pintype "passive"))
      (node (ref "S1") (pin "8") (pinfunction "8_8") (pintype "passive"))
      (node (ref "X2") (pin "2") (pinfunction "S_2") (pintype "passive"))
      (node (ref "X4") (pin "1") (pinfunction "S_1") (pintype "passive"))
    )
    (net (code "44") (name "Net-(ANT1-Pad1)") (class "Default")
      (node (ref "ANT1") (pin "1") (pinfunction "1_1") (pintype "output"))
      (node (ref "RF") (pin "ANT") (pinfunction "ANT_ANT") (pintype "passive"))
    )
    (net (code "45") (name "Net-(B1-+)") (class "Default")
      (node (ref "B1") (pin "1") (pinfunction "+_1") (pintype "power_in"))
      (node (ref "RTC") (pin "3") (pinfunction "VBATT_3") (pintype "bidirectional"))
    )
    (net (code "46") (name "Net-(C2-Pad+)") (class "Default")
      (node (ref "C2") (pin "+") (pinfunction "+_+") (pintype "passive"))
      (node (ref "R10") (pin "1") (pinfunction "1_1") (pintype "passive"))
    )
    (net (code "47") (name "Net-(C14-Pad2)") (class "Default")
      (node (ref "C14") (pin "2") (pinfunction "2_2") (pintype "passive"))
      (node (ref "R35") (pin "1") (pinfunction "1_1") (pintype "passive"))
      (node (ref "R36") (pin "2") (pinfunction "2_2") (pintype "passive"))
    )
    (net (code "48") (name "Net-(C15-Pad2)") (class "Default")
      (node (ref "C15") (pin "2") (pinfunction "2_2") (pintype "passive"))
      (node (ref "R37") (pin "1") (pinfunction "1_1") (pintype "passive"))
      (node (ref "R38") (pin "2") (pinfunction "2_2") (pintype "passive"))
    )
    (net (code "49") (name "Net-(C16-Pad2)") (class "Default")
      (node (ref "C16") (pin "2") (pinfunction "2_2") (pintype "passive"))
      (node (ref "C17") (pin "2") (pinfunction "2_2") (pintype "passive"))
      (node (ref "R39") (pin "1") (pinfunction "1_1") (pintype "passive"))
      (node (ref "R40") (pin "2") (pinfunction "2_2") (pintype "passive"))
    )
    (net (code "50") (name "Net-(K1A-1)") (class "Default")
      (node (ref "D1") (pin "A") (pinfunction "A_A") (pintype "passive"))
      (node (ref "K1") (pin "A1") (pinfunction "1_A1") (pintype "passive"))
      (node (ref "LED1") (pin "K") (pinfunction "C_K") (pintype "passive"))
      (node (ref "T5") (pin "3") (pinfunction "C_3") (pintype "passive"))
    )
    (net (code "51") (name "Net-(K1B-P)") (class "Default")
      (node (ref "K1") (pin "11") (pinfunction "P_11") (pintype "passive"))
      (node (ref "X1") (pin "6") (pinfunction "KL_6") (pintype "passive"))
    )
    (net (code "52") (name "Net-(K2A-1)") (class "Default")
      (node (ref "D2") (pin "A") (pinfunction "A_A") (pintype "passive"))
      (node (ref "K2") (pin "A1") (pinfunction "1_A1") (pintype "passive"))
      (node (ref "LED2") (pin "K") (pinfunction "C_K") (pintype "passive"))
      (node (ref "T6") (pin "3") (pinfunction "C_3") (pintype "passive"))
    )
    (net (code "53") (name "Net-(K2B-P)") (class "Default")
      (node (ref "K2") (pin "11") (pinfunction "P_11") (pintype "passive"))
      (node (ref "X1") (pin "5") (pinfunction "KL_5") (pintype "passive"))
    )
    (net (code "54") (name "Net-(K3A-1)") (class "Default")
      (node (ref "D3") (pin "A") (pinfunction "A_A") (pintype "passive"))
      (node (ref "K3") (pin "A1") (pinfunction "1_A1") (pintype "passive"))
      (node (ref "LED4") (pin "K") (pinfunction "C_K") (pintype "passive"))
      (node (ref "T7") (pin "3") (pinfunction "C_3") (pintype "passive"))
    )
    (net (code "55") (name "Net-(K3B-P)") (class "Default")
      (node (ref "K3") (pin "11") (pinfunction "P_11") (pintype "passive"))
      (node (ref "X1") (pin "4") (pinfunction "KL_4") (pintype "passive"))
    )
    (net (code "56") (name "Net-(K4A-1)") (class "Default")
      (node (ref "D4") (pin "A") (pinfunction "A_A") (pintype "passive"))
      (node (ref "K4") (pin "A1") (pinfunction "1_A1") (pintype "passive"))
      (node (ref "LED5") (pin "K") (pinfunction "C_K") (pintype "passive"))
      (node (ref "T8") (pin "3") (pinfunction "C_3") (pintype "passive"))
    )
    (net (code "57") (name "Net-(K4B-P)") (class "Default")
      (node (ref "K4") (pin "11") (pinfunction "P_11") (pintype "passive"))
      (node (ref "X1") (pin "3") (pinfunction "KL_3") (pintype "passive"))
    )
    (net (code "58") (name "Net-(LED1-PadA)") (class "Default")
      (node (ref "LED1") (pin "A") (pinfunction "A_A") (pintype "passive"))
      (node (ref "R42") (pin "2") (pinfunction "2_2") (pintype "passive"))
    )
    (net (code "59") (name "Net-(LED2-PadA)") (class "Default")
      (node (ref "LED2") (pin "A") (pinfunction "A_A") (pintype "passive"))
      (node (ref "R44") (pin "2") (pinfunction "2_2") (pintype "passive"))
    )
    (net (code "60") (name "Net-(LED4-PadA)") (class "Default")
      (node (ref "LED4") (pin "A") (pinfunction "A_A") (pintype "passive"))
      (node (ref "R51") (pin "2") (pinfunction "2_2") (pintype "passive"))
    )
    (net (code "61") (name "Net-(LED5-PadA)") (class "Default")
      (node (ref "LED5") (pin "A") (pinfunction "A_A") (pintype "passive"))
      (node (ref "R52") (pin "2") (pinfunction "2_2") (pintype "passive"))
    )
    (net (code "62") (name "Net-(OK1-A)") (class "Default")
      (node (ref "OK1") (pin "1") (pinfunction "A_1") (pintype "passive"))
      (node (ref "R45") (pin "2") (pinfunction "2_2") (pintype "passive"))
    )
    (net (code "63") (name "Net-(OK1-EMIT)") (class "Default")
      (node (ref "OK1") (pin "3") (pinfunction "EMIT_3") (pintype "passive"))
      (node (ref "R41") (pin "2") (pinfunction "2_2") (pintype "passive"))
    )
    (net (code "64") (name "Net-(OK2-A)") (class "Default")
      (node (ref "OK2") (pin "1") (pinfunction "A_1") (pintype "passive"))
      (node (ref "R46") (pin "1") (pinfunction "1_1") (pintype "passive"))
    )
    (net (code "65") (name "Net-(OK2-EMIT)") (class "Default")
      (node (ref "OK2") (pin "3") (pinfunction "EMIT_3") (pintype "passive"))
      (node (ref "R43") (pin "2") (pinfunction "2_2") (pintype "passive"))
    )
    (net (code "66") (name "Net-(OK3-A)") (class "Default")
      (node (ref "OK3") (pin "1") (pinfunction "A_1") (pintype "passive"))
      (node (ref "R47") (pin "2") (pinfunction "2_2") (pintype "passive"))
    )
    (net (code "67") (name "Net-(OK3-EMIT)") (class "Default")
      (node (ref "OK3") (pin "3") (pinfunction "EMIT_3") (pintype "passive"))
      (node (ref "R49") (pin "2") (pinfunction "2_2") (pintype "passive"))
    )
    (net (code "68") (name "Net-(OK4-A)") (class "Default")
      (node (ref "OK4") (pin "1") (pinfunction "A_1") (pintype "passive"))
      (node (ref "R27") (pin "2") (pinfunction "2_2") (pintype "passive"))
    )
    (net (code "69") (name "Net-(OK4-A1)") (class "Default")
      (node (ref "OK4") (pin "4") (pinfunction "A1_4") (pintype "passive"))
      (node (ref "T1") (pin "G") (pinfunction "G_G") (pintype "passive"))
    )
    (net (code "70") (name "Net-(OK4-A2)") (class "Default")
      (node (ref "OK4") (pin "6") (pinfunction "A2_6") (pintype "passive"))
      (node (ref "R28") (pin "1") (pinfunction "1_1") (pintype "passive"))
    )
    (net (code "71") (name "Net-(OK5-A)") (class "Default")
      (node (ref "OK5") (pin "1") (pinfunction "A_1") (pintype "passive"))
      (node (ref "R29") (pin "2") (pinfunction "2_2") (pintype "passive"))
    )
    (net (code "72") (name "Net-(OK5-A1)") (class "Default")
      (node (ref "OK5") (pin "4") (pinfunction "A1_4") (pintype "passive"))
      (node (ref "T2") (pin "G") (pinfunction "G_G") (pintype "passive"))
    )
    (net (code "73") (name "Net-(OK5-A2)") (class "Default")
      (node (ref "OK5") (pin "6") (pinfunction "A2_6") (pintype "passive"))
      (node (ref "R30") (pin "1") (pinfunction "1_1") (pintype "passive"))
    )
    (net (code "74") (name "Net-(OK6-A)") (class "Default")
      (node (ref "OK6") (pin "1") (pinfunction "A_1") (pintype "passive"))
      (node (ref "R31") (pin "2") (pinfunction "2_2") (pintype "passive"))
    )
    (net (code "75") (name "Net-(OK6-A1)") (class "Default")
      (node (ref "OK6") (pin "4") (pinfunction "A1_4") (pintype "passive"))
      (node (ref "T3") (pin "G") (pinfunction "G_G") (pintype "passive"))
    )
    (net (code "76") (name "Net-(OK6-A2)") (class "Default")
      (node (ref "OK6") (pin "6") (pinfunction "A2_6") (pintype "passive"))
      (node (ref "R32") (pin "2") (pinfunction "2_2") (pintype "passive"))
    )
    (net (code "77") (name "Net-(OK7-A)") (class "Default")
      (node (ref "OK7") (pin "1") (pinfunction "A_1") (pintype "passive"))
      (node (ref "R33") (pin "2") (pinfunction "2_2") (pintype "passive"))
    )
    (net (code "78") (name "Net-(OK7-A1)") (class "Default")
      (node (ref "OK7") (pin "4") (pinfunction "A1_4") (pintype "passive"))
      (node (ref "T4") (pin "G") (pinfunction "G_G") (pintype "passive"))
    )
    (net (code "79") (name "Net-(OK7-A2)") (class "Default")
      (node (ref "OK7") (pin "6") (pinfunction "A2_6") (pintype "passive"))
      (node (ref "R34") (pin "1") (pinfunction "1_1") (pintype "passive"))
    )
    (net (code "80") (name "Net-(OK8-A)") (class "Default")
      (node (ref "OK8") (pin "1") (pinfunction "A_1") (pintype "passive"))
      (node (ref "R48") (pin "2") (pinfunction "2_2") (pintype "passive"))
    )
    (net (code "81") (name "Net-(OK8-EMIT)") (class "Default")
      (node (ref "OK8") (pin "3") (pinfunction "EMIT_3") (pintype "passive"))
      (node (ref "R50") (pin "2") (pinfunction "2_2") (pintype "passive"))
    )
    (net (code "82") (name "Net-(Q2-B)") (class "Default")
      (node (ref "Q2") (pin "1") (pinfunction "B_1") (pintype "passive"))
      (node (ref "R14") (pin "1") (pinfunction "1_1") (pintype "passive"))
    )
    (net (code "83") (name "Net-(Q2-C)") (class "Default")
      (node (ref "Q2") (pin "3") (pinfunction "C_3") (pintype "passive"))
      (node (ref "R15") (pin "1") (pinfunction "1_1") (pintype "passive"))
    )
    (net (code "84") (name "Net-(RFLED-C)") (class "Default")
      (node (ref "R15") (pin "2") (pinfunction "2_2") (pintype "passive"))
      (node (ref "RFLED") (pin "K") (pinfunction "C_K") (pintype "passive"))
    )
    (net (code "85") (name "Net-(RTC-X1)") (class "Default")
      (node (ref "RTC") (pin "1") (pinfunction "X1_1") (pintype "bidirectional"))
      (node (ref "Y1") (pin "1") (pinfunction "1_1") (pintype "passive"))
    )
    (net (code "86") (name "Net-(RTC-X2)") (class "Default")
      (node (ref "RTC") (pin "2") (pinfunction "X2_2") (pintype "bidirectional"))
      (node (ref "Y1") (pin "2") (pinfunction "2_2") (pintype "passive"))
    )
    (net (code "87") (name "Net-(T1-A1)") (class "Default")
      (node (ref "C14") (pin "1") (pinfunction "1_1") (pintype "passive"))
      (node (ref "R35") (pin "2") (pinfunction "2_2") (pintype "passive"))
      (node (ref "T1") (pin "T1") (pinfunction "A1_T1") (pintype "passive"))
    )
    (net (code "88") (name "Net-(T2-A1)") (class "Default")
      (node (ref "C15") (pin "1") (pinfunction "1_1") (pintype "passive"))
      (node (ref "R37") (pin "2") (pinfunction "2_2") (pintype "passive"))
      (node (ref "T2") (pin "T1") (pinfunction "A1_T1") (pintype "passive"))
    )
    (net (code "89") (name "Net-(T3-A1)") (class "Default")
      (node (ref "C16") (pin "1") (pinfunction "1_1") (pintype "passive"))
      (node (ref "C17") (pin "1") (pinfunction "1_1") (pintype "passive"))
      (node (ref "R39") (pin "2") (pinfunction "2_2") (pintype "passive"))
      (node (ref "T3") (pin "T1") (pinfunction "A1_T1") (pintype "passive"))
    )
    (net (code "90") (name "Net-(T5-B)") (class "Default")
      (node (ref "R41") (pin "1") (pinfunction "1_1") (pintype "passive"))
      (node (ref "T5") (pin "2") (pinfunction "B_2") (pintype "passive"))
    )
    (net (code "91") (name "Net-(T6-B)") (class "Default")
      (node (ref "R43") (pin "1") (pinfunction "1_1") (pintype "passive"))
      (node (ref "T6") (pin "2") (pinfunction "B_2") (pintype "passive"))
    )
    (net (code "92") (name "Net-(T7-B)") (class "Default")
      (node (ref "R49") (pin "1") (pinfunction "1_1") (pintype "passive"))
      (node (ref "T7") (pin "2") (pinfunction "B_2") (pintype "passive"))
    )
    (net (code "93") (name "Net-(T8-B)") (class "Default")
      (node (ref "R50") (pin "1") (pinfunction "1_1") (pintype "passive"))
      (node (ref "T8") (pin "2") (pinfunction "B_2") (pintype "passive"))
    )
    (net (code "94") (name "unconnected-(JP1-GP4-Pad7)") (class "Default")
      (node (ref "JP1") (pin "7") (pinfunction "GP4_7") (pintype "bidirectional"))
    )
    (net (code "95") (name "unconnected-(JP1-GP18#-Pad12)") (class "Default")
      (node (ref "JP1") (pin "12") (pinfunction "GP18#_12") (pintype "bidirectional"))
    )
    (net (code "96") (name "unconnected-(JP1-GP23-Pad16)") (class "Default")
      (node (ref "JP1") (pin "16") (pinfunction "GP23_16") (pintype "bidirectional"))
    )
    (net (code "97") (name "unconnected-(JP1-ID_SC-Pad28)") (class "Default")
      (node (ref "JP1") (pin "28") (pinfunction "ID_SC_28") (pintype "bidirectional"))
    )
    (net (code "98") (name "unconnected-(JP1-ID_SD-Pad27)") (class "Default")
      (node (ref "JP1") (pin "27") (pinfunction "ID_SD_27") (pintype "bidirectional"))
    )
    (net (code "99") (name "unconnected-(RTC-SQW-Pad7)") (class "Default")
      (node (ref "RTC") (pin "7") (pinfunction "SQW_7") (pintype "bidirectional"))
    )
    (net (code "100") (name "unconnected-(X2C-S-Pad3)") (class "Default")
      (node (ref "X2") (pin "3") (pinfunction "S_3") (pintype "passive"))
    )
  )
)
